# Power.net
KiCad netlist of a schematic drawn in Altium Designer
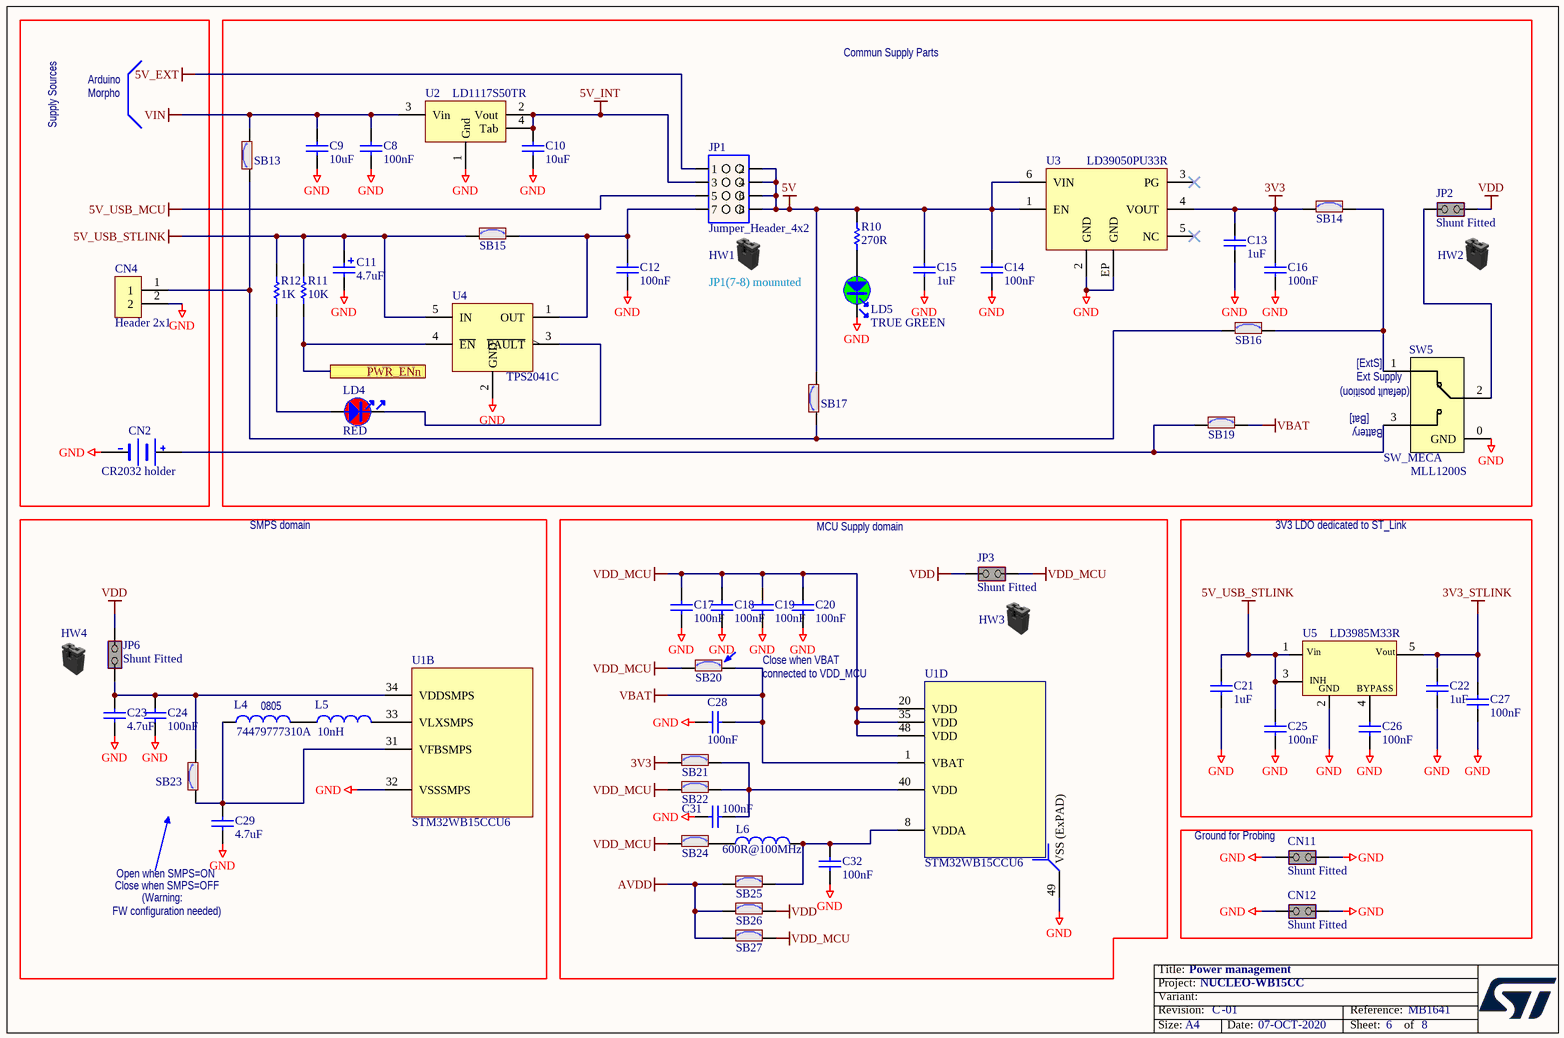
[diagram p0: Power.SchDoc]

(export (version "E")
  (design (tool "Eeschema 10.0.6"))
  (components
    (comp (ref "C8")
      (value "100nF")
      (footprint "C0603")
      (description "Capacitor, MLCC, 100nF, 50V, X7R, +/-10%, 0603, T=0.8mm")
      (fields
        (field (name "INTERNAL_PART_NUMBER") "MCD-01099")
        (field (name "MANUFACTURER_PART_NUMBER") "CC0603KRX7R9BB104")
      )
      (libsource (lib "MCD_PARTS_database") (part "Capacitor"))
    )
    (comp (ref "C9")
      (value "10uF")
      (footprint "C0805")
      (description "Capacitor, MLCC, 10uF, 25V, X5R, +/-10%, 0805, T=0,85mm")
      (fields
        (field (name "INTERNAL_PART_NUMBER") "MCD-00014")
        (field (name "MANUFACTURER_PART_NUMBER") "CC0805KRX5R8BB106")
      )
      (libsource (lib "MCD_PARTS_database") (part "Capacitor"))
    )
    (comp (ref "C10")
      (value "10uF")
      (footprint "C0805")
      (description "Capacitor, MLCC, 10uF, 25V, X5R, +/-10%, 0805, T=0,85mm")
      (fields
        (field (name "INTERNAL_PART_NUMBER") "MCD-00014")
        (field (name "MANUFACTURER_PART_NUMBER") "CC0805KRX5R8BB106")
      )
      (libsource (lib "MCD_PARTS_database") (part "Capacitor"))
    )
    (comp (ref "C11")
      (value "4.7uF")
      (footprint "CPOL_TAJ-A_1206_H180")
      (description "Capacitor, Tantalum, 4.7uF, 16V, 4ohms, +/-10%, pkg Type_A (3216 metric), T=1.6mm")
      (fields
        (field (name "INTERNAL_PART_NUMBER") "MCD-00007")
        (field (name "MANUFACTURER_PART_NUMBER") "TAJA475K016R")
      )
      (libsource (lib "MCD_PARTS_database") (part "Cap_POL_TANA"))
    )
    (comp (ref "C12")
      (value "100nF")
      (footprint "C0402")
      (description "Capacitor, MLCC, 100nF, 16V, X7R, +/-10%, 0402, T=0.5mm")
      (fields
        (field (name "INTERNAL_PART_NUMBER") "MCD-00006")
        (field (name "MANUFACTURER_PART_NUMBER") "CC0402KRX7R7BB104")
      )
      (libsource (lib "MCD_PARTS_database") (part "Capacitor"))
    )
    (comp (ref "C13")
      (value "1uF")
      (footprint "C0603")
      (description "Capacitor, MLCC, 1uF, 16V, X5R, +/-10%, 0603, T=0,8mm")
      (fields
        (field (name "INTERNAL_PART_NUMBER") "MCD-00010")
        (field (name "MANUFACTURER_PART_NUMBER") "CC0603KRX5R7BB105")
      )
      (libsource (lib "MCD_PARTS_database") (part "Capacitor"))
    )
    (comp (ref "C14")
      (value "100nF")
      (footprint "C0402")
      (description "Capacitor, MLCC, 100nF, 16V, X7R, +/-10%, 0402, T=0.5mm")
      (fields
        (field (name "INTERNAL_PART_NUMBER") "MCD-00006")
        (field (name "MANUFACTURER_PART_NUMBER") "CC0402KRX7R7BB104")
      )
      (libsource (lib "MCD_PARTS_database") (part "Capacitor"))
    )
    (comp (ref "C15")
      (value "1uF")
      (footprint "C0603")
      (description "Capacitor, MLCC, 1uF, 16V, X5R, +/-10%, 0603, T=0,8mm")
      (fields
        (field (name "INTERNAL_PART_NUMBER") "MCD-00010")
        (field (name "MANUFACTURER_PART_NUMBER") "CC0603KRX5R7BB105")
      )
      (libsource (lib "MCD_PARTS_database") (part "Capacitor"))
    )
    (comp (ref "C16")
      (value "100nF")
      (footprint "C0402")
      (description "Capacitor, MLCC, 100nF, 16V, X7R, +/-10%, 0402, T=0.5mm")
      (fields
        (field (name "INTERNAL_PART_NUMBER") "MCD-00006")
        (field (name "MANUFACTURER_PART_NUMBER") "CC0402KRX7R7BB104")
      )
      (libsource (lib "MCD_PARTS_database") (part "Capacitor"))
    )
    (comp (ref "C17")
      (value "100nF")
      (footprint "C0402")
      (description "Capacitor, MLCC, 100nF, 16V, X7R, +/-10%, 0402, T=0.5mm")
      (fields
        (field (name "INTERNAL_PART_NUMBER") "MCD-00006")
        (field (name "MANUFACTURER_PART_NUMBER") "CC0402KRX7R7BB104")
      )
      (libsource (lib "MCD_PARTS_database") (part "Capacitor"))
    )
    (comp (ref "C18")
      (value "100nF")
      (footprint "C0402")
      (description "Capacitor, MLCC, 100nF, 16V, X7R, +/-10%, 0402, T=0.5mm")
      (fields
        (field (name "INTERNAL_PART_NUMBER") "MCD-00006")
        (field (name "MANUFACTURER_PART_NUMBER") "CC0402KRX7R7BB104")
      )
      (libsource (lib "MCD_PARTS_database") (part "Capacitor"))
    )
    (comp (ref "C19")
      (value "100nF")
      (footprint "C0402")
      (description "Capacitor, MLCC, 100nF, 16V, X7R, +/-10%, 0402, T=0.5mm")
      (fields
        (field (name "INTERNAL_PART_NUMBER") "MCD-00006")
        (field (name "MANUFACTURER_PART_NUMBER") "CC0402KRX7R7BB104")
      )
      (libsource (lib "MCD_PARTS_database") (part "Capacitor"))
    )
    (comp (ref "C20")
      (value "100nF")
      (footprint "C0402")
      (description "Capacitor, MLCC, 100nF, 16V, X7R, +/-10%, 0402, T=0.5mm")
      (fields
        (field (name "INTERNAL_PART_NUMBER") "MCD-00006")
        (field (name "MANUFACTURER_PART_NUMBER") "CC0402KRX7R7BB104")
      )
      (libsource (lib "MCD_PARTS_database") (part "Capacitor"))
    )
    (comp (ref "C21")
      (value "1uF")
      (footprint "C0603")
      (description "Capacitor, MLCC, 1uF, 16V, X5R, +/-10%, 0603, T=0,8mm")
      (fields
        (field (name "INTERNAL_PART_NUMBER") "MCD-00010")
        (field (name "MANUFACTURER_PART_NUMBER") "CC0603KRX5R7BB105")
      )
      (libsource (lib "MCD_PARTS_database") (part "Capacitor"))
    )
    (comp (ref "C22")
      (value "1uF")
      (footprint "C0603")
      (description "Capacitor, MLCC, 1uF, 16V, X5R, +/-10%, 0603, T=0,8mm")
      (fields
        (field (name "INTERNAL_PART_NUMBER") "MCD-00010")
        (field (name "MANUFACTURER_PART_NUMBER") "CC0603KRX5R7BB105")
      )
      (libsource (lib "MCD_PARTS_database") (part "Capacitor"))
    )
    (comp (ref "C23")
      (value "4.7uF")
      (footprint "C0402")
      (description "Capacitor, MLCC, 4.7uF, 6V3, X5R, +/-20%, 0402, T=0,5mm")
      (fields
        (field (name "INTERNAL_PART_NUMBER") "MCD-01356")
        (field (name "MANUFACTURER_PART_NUMBER") "GRM155R60J475ME47")
      )
      (libsource (lib "MCD_PARTS_database") (part "Capacitor"))
    )
    (comp (ref "C24")
      (value "100nF")
      (footprint "C0402")
      (description "Capacitor, MLCC, 100nF, 16V, X7R, +/-10%, 0402, T=0.5mm")
      (fields
        (field (name "INTERNAL_PART_NUMBER") "MCD-00006")
        (field (name "MANUFACTURER_PART_NUMBER") "CC0402KRX7R7BB104")
      )
      (libsource (lib "MCD_PARTS_database") (part "Capacitor"))
    )
    (comp (ref "C25")
      (value "100nF")
      (footprint "C0402")
      (description "Capacitor, MLCC, 100nF, 16V, X7R, +/-10%, 0402, T=0.5mm")
      (fields
        (field (name "INTERNAL_PART_NUMBER") "MCD-00006")
        (field (name "MANUFACTURER_PART_NUMBER") "CC0402KRX7R7BB104")
      )
      (libsource (lib "MCD_PARTS_database") (part "Capacitor"))
    )
    (comp (ref "C26")
      (value "100nF")
      (footprint "C0402")
      (description "Capacitor, MLCC, 100nF, 16V, X7R, +/-10%, 0402, T=0.5mm")
      (fields
        (field (name "INTERNAL_PART_NUMBER") "MCD-00006")
        (field (name "MANUFACTURER_PART_NUMBER") "CC0402KRX7R7BB104")
      )
      (libsource (lib "MCD_PARTS_database") (part "Capacitor"))
    )
    (comp (ref "C27")
      (value "100nF")
      (footprint "C0402")
      (description "Capacitor, MLCC, 100nF, 16V, X7R, +/-10%, 0402, T=0.5mm")
      (fields
        (field (name "INTERNAL_PART_NUMBER") "MCD-00006")
        (field (name "MANUFACTURER_PART_NUMBER") "CC0402KRX7R7BB104")
      )
      (libsource (lib "MCD_PARTS_database") (part "Capacitor"))
    )
    (comp (ref "C28")
      (value "100nF")
      (footprint "C0402")
      (description "Capacitor, MLCC, 100nF, 16V, X7R, +/-10%, 0402, T=0.5mm")
      (fields
        (field (name "INTERNAL_PART_NUMBER") "MCD-00006")
        (field (name "MANUFACTURER_PART_NUMBER") "CC0402KRX7R7BB104")
      )
      (libsource (lib "MCD_PARTS_database") (part "Capacitor"))
    )
    (comp (ref "C29")
      (value "4.7uF")
      (footprint "C0402")
      (description "Capacitor, MLCC, 4.7uF, 6V3, X5R, +/-20%, 0402, T=0,5mm")
      (fields
        (field (name "INTERNAL_PART_NUMBER") "MCD-01356")
        (field (name "MANUFACTURER_PART_NUMBER") "GRM155R60J475ME47")
      )
      (libsource (lib "MCD_PARTS_database") (part "Capacitor"))
    )
    (comp (ref "C31")
      (value "100nF")
      (footprint "C0402")
      (description "Capacitor, MLCC, 100nF, 16V, X7R, +/-10%, 0402, T=0.5mm")
      (fields
        (field (name "INTERNAL_PART_NUMBER") "MCD-00006")
        (field (name "MANUFACTURER_PART_NUMBER") "CC0402KRX7R7BB104")
      )
      (libsource (lib "MCD_PARTS_database") (part "Capacitor"))
    )
    (comp (ref "C32")
      (value "100nF")
      (footprint "C0402")
      (description "Capacitor, MLCC, 100nF, 16V, X7R, +/-10%, 0402, T=0.5mm")
      (fields
        (field (name "INTERNAL_PART_NUMBER") "MCD-00006")
        (field (name "MANUFACTURER_PART_NUMBER") "CC0402KRX7R7BB104")
      )
      (libsource (lib "MCD_PARTS_database") (part "Capacitor"))
    )
    (comp (ref "CN2")
      (value "CR2032 holder")
      (footprint "BAT_RENATA-SMTU2032-LF_KEYSTONE-1769533_CR2032_SMD_2P_DI")
      (description "Battery Coin Cell holder, CR2032_20mm, Height 5.4mm")
      (fields
        (field (name "INTERNAL_PART_NUMBER") "MCD-02071")
        (field (name "MANUFACTURER_PART_NUMBER") "SMTU2032-LF")
      )
      (libsource (lib "MCD_PARTS_database") (part "BATTERY HOLDER"))
    )
    (comp (ref "CN4")
      (value "Header 2x1")
      (footprint "CON_SAMTEC_TSW-102-07-G-S")
      (description "Header, 2x1, 2,54mm, VR, TH, Height 5.84mm/2.54mm")
      (fields
        (field (name "INTERNAL_PART_NUMBER") "MCD-00032")
        (field (name "MANUFACTURER_PART_NUMBER") "TSW-102-07-G-S")
      )
      (libsource (lib "MCD_PARTS_database") (part "Header 2x1"))
    )
    (comp (ref "CN11")
      (value "Shunt Fitted")
      (footprint "CON_SAMTEC_TSW-102-07-G-S")
      (description "Header, 2x1, 2,54mm, VR, TH, Height 5.84mm/2.54mm - Shunt Fitted by default")
      (fields
        (field (name "INTERNAL_PART_NUMBER") "MCD-00683")
        (field (name "MANUFACTURER_PART_NUMBER") "TSW-102-07-G-S")
      )
      (libsource (lib "") (part "Jumper_Header 2x1 Fitted_1"))
    )
    (comp (ref "CN12")
      (value "Shunt Fitted")
      (footprint "CON_SAMTEC_TSW-102-07-G-S")
      (description "Header, 2x1, 2,54mm, VR, TH, Height 5.84mm/2.54mm - Shunt Fitted by default")
      (fields
        (field (name "INTERNAL_PART_NUMBER") "MCD-00683")
        (field (name "MANUFACTURER_PART_NUMBER") "TSW-102-07-G-S")
      )
      (libsource (lib "") (part "Jumper_Header 2x1 Fitted_1"))
    )
    (comp (ref "HW1")
      (value "Shunt Black 2.54mm")
      (description "SHUNT 2.54mm BLACK")
      (fields
        (field (name "INTERNAL_PART_NUMBER") "MCD-00043")
        (field (name "MANUFACTURER_PART_NUMBER") "SNT-100-BK-G")
      )
      (libsource (lib "MCD_PARTS_database") (part "Shunt Black 2.54mm"))
    )
    (comp (ref "HW2")
      (value "Shunt Black 2.54mm")
      (description "SHUNT 2.54mm BLACK")
      (fields
        (field (name "INTERNAL_PART_NUMBER") "MCD-00043")
        (field (name "MANUFACTURER_PART_NUMBER") "SNT-100-BK-G")
      )
      (libsource (lib "MCD_PARTS_database") (part "Shunt Black 2.54mm"))
    )
    (comp (ref "HW3")
      (value "Shunt Black 2.54mm")
      (description "SHUNT 2.54mm BLACK")
      (fields
        (field (name "INTERNAL_PART_NUMBER") "MCD-00043")
        (field (name "MANUFACTURER_PART_NUMBER") "SNT-100-BK-G")
      )
      (libsource (lib "MCD_PARTS_database") (part "Shunt Black 2.54mm"))
    )
    (comp (ref "HW4")
      (value "Shunt Black 2.54mm")
      (description "SHUNT 2.54mm BLACK")
      (fields
        (field (name "INTERNAL_PART_NUMBER") "MCD-00043")
        (field (name "MANUFACTURER_PART_NUMBER") "SNT-100-BK-G")
      )
      (libsource (lib "MCD_PARTS_database") (part "Shunt Black 2.54mm"))
    )
    (comp (ref "JP1")
      (value "Jumper_Header_4x2")
      (footprint "CON_SAMTEC_TSW-104-07-X-D")
      (description "Header, 4x2, 2,54mm, VR, TH, Height 5.84mm/2.54mm")
      (fields
        (field (name "INTERNAL_PART_NUMBER") "MCD-00633")
        (field (name "MANUFACTURER_PART_NUMBER") "TSW-104-07-G-D")
      )
      (libsource (lib "MCD_PARTS_database") (part "Jumper_Header 4x2"))
    )
    (comp (ref "JP2")
      (value "Shunt Fitted")
      (footprint "CON_SAMTEC_TSW-102-07-G-S")
      (description "Header, 2x1, 2,54mm, VR, TH, Height 5.84mm/2.54mm - Shunt Fitted by default")
      (fields
        (field (name "INTERNAL_PART_NUMBER") "MCD-00683")
        (field (name "MANUFACTURER_PART_NUMBER") "TSW-102-07-G-S")
      )
      (libsource (lib "") (part "Jumper_Header 2x1 Fitted_2"))
    )
    (comp (ref "JP3")
      (value "Shunt Fitted")
      (footprint "CON_SAMTEC_TSW-102-07-G-S")
      (description "Header, 2x1, 2,54mm, VR, TH, Height 5.84mm/2.54mm - Shunt Fitted by default")
      (fields
        (field (name "INTERNAL_PART_NUMBER") "MCD-00683")
        (field (name "MANUFACTURER_PART_NUMBER") "TSW-102-07-G-S")
      )
      (libsource (lib "") (part "Jumper_Header 2x1 Fitted_2"))
    )
    (comp (ref "JP6")
      (value "Shunt Fitted")
      (footprint "CON_SAMTEC_TSW-102-07-G-S")
      (description "Header, 2x1, 2,54mm, VR, TH, Height 5.84mm/2.54mm - Shunt Fitted by default")
      (fields
        (field (name "INTERNAL_PART_NUMBER") "MCD-00683")
        (field (name "MANUFACTURER_PART_NUMBER") "TSW-102-07-G-S")
      )
      (libsource (lib "MCD_PARTS_database") (part "Jumper_Header 2x1 Fitted"))
    )
    (comp (ref "L4")
      (value "74479777310A")
      (footprint "IND_0805_WURTH_74479777310A")
      (description "PMI Series 10 μH ±20% Multilayer SMD Inductor, 0805 25MHz 650mA dc 500mΩ Rdc")
      (fields
        (field (name "INTERNAL_PART_NUMBER") "MCD-01676")
        (field (name "MANUFACTURER") "WURTH ELEKTRONIK")
      )
      (libsource (lib "MCD_PARTS_database") (part "Inductor"))
    )
    (comp (ref "L5")
      (value "10nH")
      (footprint "IND_0402_MURATA_LQW15AN_H0P5")
      (description "Inductor, 10nH +-2%, 100mA max,1.3 ohm DC max, Q min = 13,0402")
      (fields
        (field (name "INTERNAL_PART_NUMBER") "MCD-02063")
        (field (name "MANUFACTURER_PART_NUMBER") "LQP15MN10NG02")
      )
      (libsource (lib "MCD_PARTS_database") (part "Inductor"))
    )
    (comp (ref "L6")
      (value "600R@100MHz")
      (footprint "L0603")
      (description "SMD Chip ferrite bead, 600R@100MHz +/-25%, 350mA, 500mohm DC, 0603, T=0.8mm")
      (fields
        (field (name "INTERNAL_PART_NUMBER") "MCD-00047")
        (field (name "MANUFACTURER_PART_NUMBER") "FCM1608KF-601T03")
      )
      (libsource (lib "MCD_PARTS_database") (part "BEAD"))
    )
    (comp (ref "LD4")
      (value "RED")
      (footprint "LED_0603_VISHAY_VLMS1300-GS08_RED_1A2K_H0P8")
      (description "LED Red, 0603 SMD, 2V Forward Voltage")
      (fields
        (field (name "INTERNAL_PART_NUMBER") "MCD-00587")
        (field (name "MANUFACTURER_PART_NUMBER") "VLMS1300-GS08")
      )
      (libsource (lib "MCD_PARTS_database") (part "LED_red"))
    )
    (comp (ref "LD5")
      (value "TRUE GREEN")
      (footprint "LED_0603_VISHAY_VLMTG1300-GS08_GREEN_1A2K_H0P8")
      (description "LED Green, 0603 SMD, Fw Voltage = 2.8V - 3.6V")
      (fields
        (field (name "INTERNAL_PART_NUMBER") "MCD-00589")
        (field (name "MANUFACTURER_PART_NUMBER") "VLMTG1300-GS08")
      )
      (libsource (lib "MCD_PARTS_database") (part "LED_green"))
    )
    (comp (ref "R10")
      (value "270R")
      (footprint "R0402")
      (description "Resistor,270R,0402,1%,1/16W")
      (fields
        (field (name "INTERNAL_PART_NUMBER") "MCD-00441")
        (field (name "MANUFACTURER_PART_NUMBER") "RC0402FR-07270RL")
      )
      (libsource (lib "MCD_PARTS_database") (part "Resistor"))
    )
    (comp (ref "R11")
      (value "10K")
      (footprint "R0402")
      (description "Resistor,10K,0402,1%,1/16W")
      (fields
        (field (name "INTERNAL_PART_NUMBER") "MCD-00053")
        (field (name "MANUFACTURER_PART_NUMBER") "RC0402FR-0710KL")
      )
      (libsource (lib "MCD_PARTS_database") (part "Resistor"))
    )
    (comp (ref "R12")
      (value "1K")
      (footprint "R0402")
      (description "Resistor,1K,0402,1%,1/16W")
      (fields
        (field (name "INTERNAL_PART_NUMBER") "MCD-00061")
        (field (name "MANUFACTURER_PART_NUMBER") "RC0402FR-071KL")
      )
      (libsource (lib "MCD_PARTS_database") (part "Resistor"))
    )
    (comp (ref "SB13")
      (value "SB_ON")
      (footprint "SOLDER-BRIDGE_R0402-0R")
      (description "Solder Bridge 0402 ON")
      (fields
        (field (name "INTERNAL_PART_NUMBER") "MCD-01618")
        (field (name "MANUFACTURER_PART_NUMBER") "RC0402JR-070RL")
      )
      (libsource (lib "MCD_PARTS_database") (part "SB_ON"))
    )
    (comp (ref "SB14")
      (value "SB_ON")
      (footprint "SOLDER-BRIDGE_R0402-0R")
      (description "Solder Bridge 0402 ON")
      (fields
        (field (name "INTERNAL_PART_NUMBER") "MCD-01618")
        (field (name "MANUFACTURER_PART_NUMBER") "RC0402JR-070RL")
      )
      (libsource (lib "") (part "SB_ON_1"))
    )
    (comp (ref "SB15")
      (value "SB_ON")
      (footprint "SOLDER-BRIDGE_R0402-0R")
      (description "Solder Bridge 0402 ON")
      (fields
        (field (name "INTERNAL_PART_NUMBER") "MCD-01618")
        (field (name "MANUFACTURER_PART_NUMBER") "RC0402JR-070RL")
      )
      (libsource (lib "") (part "SB_ON_1"))
    )
    (comp (ref "SB16")
      (value "SB_ON")
      (footprint "SOLDER-BRIDGE_R0402-0R")
      (description "Solder Bridge 0402 ON")
      (fields
        (field (name "INTERNAL_PART_NUMBER") "MCD-01618")
        (field (name "MANUFACTURER_PART_NUMBER") "RC0402JR-070RL")
      )
      (libsource (lib "") (part "SB_ON_1"))
    )
    (comp (ref "SB17")
      (value "SB_ON")
      (footprint "SOLDER-BRIDGE_R0402-0R")
      (description "Solder Bridge 0402 ON")
      (fields
        (field (name "INTERNAL_PART_NUMBER") "MCD-01618")
        (field (name "MANUFACTURER_PART_NUMBER") "RC0402JR-070RL")
      )
      (libsource (lib "MCD_PARTS_database") (part "SB_ON"))
    )
    (comp (ref "SB19")
      (value "SB_ON")
      (footprint "SOLDER-BRIDGE_R0402-0R")
      (description "Solder Bridge 0402 ON")
      (fields
        (field (name "INTERNAL_PART_NUMBER") "MCD-01618")
        (field (name "MANUFACTURER_PART_NUMBER") "RC0402JR-070RL")
      )
      (libsource (lib "") (part "SB_ON_1"))
    )
    (comp (ref "SB20")
      (value "SB_ON")
      (footprint "SOLDER-BRIDGE_R0402-0R")
      (description "Solder Bridge 0402 ON")
      (fields
        (field (name "INTERNAL_PART_NUMBER") "MCD-01618")
        (field (name "MANUFACTURER_PART_NUMBER") "RC0402JR-070RL")
      )
      (libsource (lib "") (part "SB_ON_1"))
    )
    (comp (ref "SB21")
      (value "SB_ON")
      (footprint "SOLDER-BRIDGE_R0402-0R")
      (description "Solder Bridge 0402 ON")
      (fields
        (field (name "INTERNAL_PART_NUMBER") "MCD-01618")
        (field (name "MANUFACTURER_PART_NUMBER") "RC0402JR-070RL")
      )
      (libsource (lib "") (part "SB_ON_1"))
    )
    (comp (ref "SB22")
      (value "SB_ON")
      (footprint "SOLDER-BRIDGE_R0402-0R")
      (description "Solder Bridge 0402 ON")
      (fields
        (field (name "INTERNAL_PART_NUMBER") "MCD-01618")
        (field (name "MANUFACTURER_PART_NUMBER") "RC0402JR-070RL")
      )
      (libsource (lib "") (part "SB_ON_1"))
    )
    (comp (ref "SB23")
      (value "SB_ON")
      (footprint "SOLDER-BRIDGE_R0402-0R")
      (description "Solder Bridge 0402 ON")
      (fields
        (field (name "INTERNAL_PART_NUMBER") "MCD-01618")
        (field (name "MANUFACTURER_PART_NUMBER") "RC0402JR-070RL")
      )
      (libsource (lib "MCD_PARTS_database") (part "SB_ON"))
    )
    (comp (ref "SB24")
      (value "SB_ON")
      (footprint "SOLDER-BRIDGE_R0402-0R")
      (description "Solder Bridge 0402 ON")
      (fields
        (field (name "INTERNAL_PART_NUMBER") "MCD-01618")
        (field (name "MANUFACTURER_PART_NUMBER") "RC0402JR-070RL")
      )
      (libsource (lib "") (part "SB_ON_1"))
    )
    (comp (ref "SB25")
      (value "SB_ON")
      (footprint "SOLDER-BRIDGE_R0402-0R")
      (description "Solder Bridge 0402 ON")
      (fields
        (field (name "INTERNAL_PART_NUMBER") "MCD-01618")
        (field (name "MANUFACTURER_PART_NUMBER") "RC0402JR-070RL")
      )
      (libsource (lib "") (part "SB_ON_1"))
    )
    (comp (ref "SB26")
      (value "SB_ON")
      (footprint "SOLDER-BRIDGE_R0402-0R")
      (description "Solder Bridge 0402 ON")
      (fields
        (field (name "INTERNAL_PART_NUMBER") "MCD-01618")
        (field (name "MANUFACTURER_PART_NUMBER") "RC0402JR-070RL")
      )
      (libsource (lib "") (part "SB_ON_1"))
    )
    (comp (ref "SB27")
      (value "SB_ON")
      (footprint "SOLDER-BRIDGE_R0402-0R")
      (description "Solder Bridge 0402 ON")
      (fields
        (field (name "INTERNAL_PART_NUMBER") "MCD-01618")
        (field (name "MANUFACTURER_PART_NUMBER") "RC0402JR-070RL")
      )
      (libsource (lib "") (part "SB_ON_1"))
    )
    (comp (ref "SW5")
      (value "SW_MECA")
      (footprint "SWI_SPDT-RA_TE-CONNECTIVITY_MLL1200S_1P2T")
      (description "SPDT RA SMT SLIDE SWITCH")
      (fields
        (field (name "INTERNAL_PART_NUMBER") "MCD-02081")
        (field (name "ALTIUM_VALUE") "MLL1200S")
        (field (name "MANUFACTURER_PART_NUMBER") "MLL1200S")
      )
      (libsource (lib "MCD_PARTS_database") (part "SW_MECA"))
    )
    (comp (ref "U1")
      (value "STM32WB15CCU6")
      (footprint "ICC_UFQFPN48-EPAD_7X7_H0P55_P050")
      (fields
        (field (name "INTERNAL_PART_NUMBER") "MCD-02058")
        (field (name "MANUFACTURER") "STMICROELECTRONICS")
        (field (name "Comment") "STM32WB15_QFN48")
      )
      (libsource (lib "MCD_PARTS_database") (part "STM32WB15_QFN48"))
    )
    (comp (ref "U2")
      (value "LD1117S50TR")
      (footprint "REG_SOT223-TAB")
      (description "IC REG LDO 5V 0.8A SOT223")
      (fields
        (field (name "INTERNAL_PART_NUMBER") "MCD-00088")
        (field (name "MANUFACTURER") "STMICROELECTRONICS")
      )
      (libsource (lib "MCD_PARTS_database") (part "LD1117S50TR"))
    )
    (comp (ref "U3")
      (value "LD39050PU33R")
      (footprint "ICC_DFN6-EPAD_3X3_P095")
      (description "Low quiescent current and low noise voltage regulators")
      (fields
        (field (name "INTERNAL_PART_NUMBER") "MCD-00215")
        (field (name "MANUFACTURER") "STMICROELECTRONICS")
      )
      (libsource (lib "MCD_PARTS_database") (part "LD39050PU33R"))
    )
    (comp (ref "U4")
      (value "TPS2041C")
      (footprint "MOS_SOT23-5L")
      (description "5V Power Switch, 0.85A, RDSon 130mOhm max, with active low enable pin")
      (fields
        (field (name "INTERNAL_PART_NUMBER") "MCD-01785")
        (field (name "MANUFACTURER_PART_NUMBER") "TPS2041CDBVT")
      )
      (libsource (lib "MCD_PARTS_database") (part "TPS2041C"))
    )
    (comp (ref "U5")
      (value "LD3985M33R")
      (footprint "REG_SOT23-5L")
      (description "Ultra low drop-low noise BiCMOS voltage, regulators low ESR capacitors compatible")
      (fields
        (field (name "INTERNAL_PART_NUMBER") "MCD-00086")
        (field (name "MANUFACTURER") "STMICROELECTRONICS")
      )
      (libsource (lib "MCD_PARTS_database") (part "LD3985M33R"))
    )
  )
  (nets
    (net (code "1") (name "/PWR_ENn") (class "Default")
      (node (ref "R11") (pin "1") (pinfunction "1_1") (pintype "passive"))
      (node (ref "U4") (pin "4") (pinfunction "~{EN}_4") (pintype "passive"))
    )
    (net (code "2") (name "3V3") (class "Default")
      (node (ref "C13") (pin "2") (pinfunction "2_2") (pintype "passive"))
      (node (ref "C16") (pin "2") (pinfunction "2_2") (pintype "passive"))
      (node (ref "SB14") (pin "1") (pinfunction "1_1") (pintype "passive"))
      (node (ref "SB21") (pin "1") (pinfunction "1_1") (pintype "passive"))
      (node (ref "U3") (pin "4") (pinfunction "VOUT_4") (pintype "passive"))
    )
    (net (code "3") (name "3V3_STLINK") (class "Default")
      (node (ref "C22") (pin "2") (pinfunction "2_2") (pintype "passive"))
      (node (ref "C27") (pin "2") (pinfunction "2_2") (pintype "passive"))
      (node (ref "U5") (pin "5") (pinfunction "Vout_5") (pintype "passive"))
    )
    (net (code "4") (name "5V") (class "Default")
      (node (ref "C14") (pin "2") (pinfunction "2_2") (pintype "passive"))
      (node (ref "C15") (pin "2") (pinfunction "2_2") (pintype "passive"))
      (node (ref "JP1") (pin "2") (pinfunction "2_2") (pintype "passive"))
      (node (ref "JP1") (pin "4") (pinfunction "4_4") (pintype "passive"))
      (node (ref "JP1") (pin "6") (pinfunction "6_6") (pintype "passive"))
      (node (ref "JP1") (pin "8") (pinfunction "8_8") (pintype "passive"))
      (node (ref "R10") (pin "2") (pinfunction "2_2") (pintype "passive"))
      (node (ref "SB17") (pin "2") (pinfunction "2_2") (pintype "passive"))
      (node (ref "U3") (pin "1") (pinfunction "EN_1") (pintype "passive"))
      (node (ref "U3") (pin "6") (pinfunction "VIN_6") (pintype "passive"))
    )
    (net (code "5") (name "5V_EXT") (class "Default")
      (node (ref "JP1") (pin "1") (pinfunction "1_1") (pintype "passive"))
    )
    (net (code "6") (name "5V_INT") (class "Default")
      (node (ref "C10") (pin "1") (pinfunction "1_1") (pintype "passive"))
      (node (ref "JP1") (pin "3") (pinfunction "3_3") (pintype "passive"))
      (node (ref "U2") (pin "2") (pinfunction "Vout_2") (pintype "passive"))
      (node (ref "U2") (pin "4") (pinfunction "Tab_4") (pintype "passive"))
    )
    (net (code "7") (name "5V_USB_MCU") (class "Default")
      (node (ref "JP1") (pin "5") (pinfunction "5_5") (pintype "passive"))
    )
    (net (code "8") (name "5V_USB_STLINK") (class "Default")
      (node (ref "C11") (pin "1") (pinfunction "1_1") (pintype "passive"))
      (node (ref "C21") (pin "2") (pinfunction "2_2") (pintype "passive"))
      (node (ref "C25") (pin "2") (pinfunction "2_2") (pintype "passive"))
      (node (ref "R11") (pin "2") (pinfunction "2_2") (pintype "passive"))
      (node (ref "R12") (pin "2") (pinfunction "2_2") (pintype "passive"))
      (node (ref "SB15") (pin "1") (pinfunction "1_1") (pintype "passive"))
      (node (ref "U4") (pin "5") (pinfunction "IN_5") (pintype "passive"))
      (node (ref "U5") (pin "1") (pinfunction "Vin_1") (pintype "passive"))
      (node (ref "U5") (pin "3") (pinfunction "CE_3") (pintype "passive"))
    )
    (net (code "9") (name "AVDD") (class "Default")
      (node (ref "SB25") (pin "1") (pinfunction "1_1") (pintype "passive"))
      (node (ref "SB26") (pin "1") (pinfunction "1_1") (pintype "passive"))
      (node (ref "SB27") (pin "1") (pinfunction "1_1") (pintype "passive"))
    )
    (net (code "10") (name "GND") (class "Default")
      (node (ref "C10") (pin "2") (pinfunction "2_2") (pintype "passive"))
      (node (ref "C11") (pin "2") (pinfunction "2_2") (pintype "passive"))
      (node (ref "C12") (pin "1") (pinfunction "1_1") (pintype "passive"))
      (node (ref "C13") (pin "1") (pinfunction "1_1") (pintype "passive"))
      (node (ref "C14") (pin "1") (pinfunction "1_1") (pintype "passive"))
      (node (ref "C15") (pin "1") (pinfunction "1_1") (pintype "passive"))
      (node (ref "C16") (pin "1") (pinfunction "1_1") (pintype "passive"))
      (node (ref "C17") (pin "1") (pinfunction "1_1") (pintype "passive"))
      (node (ref "C18") (pin "1") (pinfunction "1_1") (pintype "passive"))
      (node (ref "C19") (pin "1") (pinfunction "1_1") (pintype "passive"))
      (node (ref "C20") (pin "1") (pinfunction "1_1") (pintype "passive"))
      (node (ref "C21") (pin "1") (pinfunction "1_1") (pintype "passive"))
      (node (ref "C22") (pin "1") (pinfunction "1_1") (pintype "passive"))
      (node (ref "C23") (pin "1") (pinfunction "1_1") (pintype "passive"))
      (node (ref "C24") (pin "1") (pinfunction "1_1") (pintype "passive"))
      (node (ref "C25") (pin "1") (pinfunction "1_1") (pintype "passive"))
      (node (ref "C26") (pin "1") (pinfunction "1_1") (pintype "passive"))
      (node (ref "C27") (pin "1") (pinfunction "1_1") (pintype "passive"))
      (node (ref "C28") (pin "2") (pinfunction "2_2") (pintype "passive"))
      (node (ref "C29") (pin "1") (pinfunction "1_1") (pintype "passive"))
      (node (ref "C31") (pin "1") (pinfunction "1_1") (pintype "passive"))
      (node (ref "C32") (pin "1") (pinfunction "1_1") (pintype "passive"))
      (node (ref "C8") (pin "1") (pinfunction "1_1") (pintype "passive"))
      (node (ref "C9") (pin "2") (pinfunction "2_2") (pintype "passive"))
      (node (ref "CN11") (pin "1") (pinfunction "COMMON_1") (pintype "passive"))
      (node (ref "CN11") (pin "2") (pinfunction "NO_2") (pintype "passive"))
      (node (ref "CN12") (pin "1") (pinfunction "COMMON_1") (pintype "passive"))
      (node (ref "CN12") (pin "2") (pinfunction "NO_2") (pintype "passive"))
      (node (ref "CN2") (pin "2") (pinfunction "-_2") (pintype "passive"))
      (node (ref "CN4") (pin "2") (pinfunction "2_2") (pintype "passive"))
      (node (ref "LD5") (pin "2") (pintype "passive"))
      (node (ref "SW5") (pin "0") (pinfunction "GND_0") (pintype "passive"))
      (node (ref "U1") (pin "32") (pinfunction "VSSSMPS_32") (pintype "passive"))
      (node (ref "U1") (pin "49") (pinfunction "VSS_(ExPAD)_49") (pintype "passive"))
      (node (ref "U2") (pin "1") (pinfunction "Gnd_1") (pintype "passive"))
      (node (ref "U3") (pin "2") (pinfunction "GND_2") (pintype "passive"))
      (node (ref "U3") (pin "EP") (pinfunction "GND_EP") (pintype "passive"))
      (node (ref "U4") (pin "2") (pinfunction "GND_2") (pintype "passive"))
      (node (ref "U5") (pin "2") (pinfunction "GND_2") (pintype "passive"))
    )
    (net (code "11") (name "Net-(C31-Pad2)") (class "Default")
      (node (ref "C31") (pin "2") (pinfunction "2_2") (pintype "passive"))
      (node (ref "SB21") (pin "2") (pinfunction "2_2") (pintype "passive"))
      (node (ref "SB22") (pin "2") (pinfunction "2_2") (pintype "passive"))
      (node (ref "U1") (pin "40") (pinfunction "VDD_40") (pintype "passive"))
    )
    (net (code "12") (name "Net-(CN2-+)") (class "Default")
      (node (ref "CN2") (pin "1") (pinfunction "+_1") (pintype "passive"))
      (node (ref "SB19") (pin "1") (pinfunction "1_1") (pintype "passive"))
      (node (ref "SW5") (pin "3") (pinfunction "3_3") (pintype "passive"))
    )
    (net (code "13") (name "Net-(CN4-Pad1)") (class "Default")
      (node (ref "CN4") (pin "1") (pinfunction "1_1") (pintype "passive"))
      (node (ref "SB13") (pin "1") (pinfunction "1_1") (pintype "passive"))
      (node (ref "SB16") (pin "1") (pinfunction "1_1") (pintype "passive"))
      (node (ref "SB17") (pin "1") (pinfunction "1_1") (pintype "passive"))
    )
    (net (code "14") (name "Net-(JP2-COMMON)") (class "Default")
      (node (ref "JP2") (pin "1") (pinfunction "COMMON_1") (pintype "passive"))
      (node (ref "SW5") (pin "2") (pinfunction "2_2") (pintype "passive"))
    )
    (net (code "15") (name "Net-(JP6-NO)") (class "Default")
      (node (ref "C23") (pin "2") (pinfunction "2_2") (pintype "passive"))
      (node (ref "C24") (pin "2") (pinfunction "2_2") (pintype "passive"))
      (node (ref "JP6") (pin "2") (pinfunction "NO_2") (pintype "passive"))
      (node (ref "SB23") (pin "2") (pinfunction "2_2") (pintype "passive"))
      (node (ref "U1") (pin "34") (pinfunction "VDDSMPS_34") (pintype "passive"))
    )
    (net (code "16") (name "Net-(L4-Pad2)") (class "Default")
      (node (ref "L4") (pin "2") (pinfunction "2_2") (pintype "passive"))
      (node (ref "L5") (pin "1") (pinfunction "1_1") (pintype "passive"))
    )
    (net (code "17") (name "Net-(L6-Pad1)") (class "Default")
      (node (ref "L6") (pin "1") (pinfunction "1_1") (pintype "passive"))
      (node (ref "SB24") (pin "2") (pinfunction "2_2") (pintype "passive"))
    )
    (net (code "18") (name "Net-(LD4-Pad1)") (class "Default")
      (node (ref "LD4") (pin "1") (pintype "passive"))
      (node (ref "R12") (pin "1") (pinfunction "1_1") (pintype "passive"))
    )
    (net (code "19") (name "Net-(LD5-Pad1)") (class "Default")
      (node (ref "LD5") (pin "1") (pintype "passive"))
      (node (ref "R10") (pin "1") (pinfunction "1_1") (pintype "passive"))
    )
    (net (code "20") (name "Net-(SB14-Pad2)") (class "Default")
      (node (ref "SB14") (pin "2") (pinfunction "2_2") (pintype "passive"))
      (node (ref "SB16") (pin "2") (pinfunction "2_2") (pintype "passive"))
      (node (ref "SW5") (pin "1") (pinfunction "1_1") (pintype "passive"))
    )
    (net (code "21") (name "Net-(U1B-VFBSMPS)") (class "Default")
      (node (ref "C29") (pin "2") (pinfunction "2_2") (pintype "passive"))
      (node (ref "L4") (pin "1") (pinfunction "1_1") (pintype "passive"))
      (node (ref "SB23") (pin "1") (pinfunction "1_1") (pintype "passive"))
      (node (ref "U1") (pin "31") (pinfunction "VFBSMPS_31") (pintype "passive"))
    )
    (net (code "22") (name "Net-(U1B-VLXSMPS)") (class "Default")
      (node (ref "L5") (pin "2") (pinfunction "2_2") (pintype "passive"))
      (node (ref "U1") (pin "33") (pinfunction "VLXSMPS_33") (pintype "passive"))
    )
    (net (code "23") (name "Net-(U1D-VDDA)") (class "Default")
      (node (ref "C32") (pin "2") (pinfunction "2_2") (pintype "passive"))
      (node (ref "L6") (pin "2") (pinfunction "2_2") (pintype "passive"))
      (node (ref "SB25") (pin "2") (pinfunction "2_2") (pintype "passive"))
      (node (ref "U1") (pin "8") (pinfunction "VDDA_8") (pintype "passive"))
    )
    (net (code "24") (name "Net-(U4-OUT)") (class "Default")
      (node (ref "C12") (pin "2") (pinfunction "2_2") (pintype "passive"))
      (node (ref "JP1") (pin "7") (pinfunction "7_7") (pintype "passive"))
      (node (ref "SB15") (pin "2") (pinfunction "2_2") (pintype "passive"))
      (node (ref "U4") (pin "1") (pinfunction "OUT_1") (pintype "passive"))
    )
    (net (code "25") (name "Net-(U4-~{FAULT})") (class "Default")
      (node (ref "LD4") (pin "2") (pintype "passive"))
      (node (ref "U4") (pin "3") (pinfunction "~{FAULT}_3") (pintype "passive"))
    )
    (net (code "26") (name "Net-(U5-BYPASS)") (class "Default")
      (node (ref "C26") (pin "2") (pinfunction "2_2") (pintype "passive"))
      (node (ref "U5") (pin "4") (pinfunction "BYPASS_4") (pintype "passive"))
    )
    (net (code "27") (name "VBAT") (class "Default")
      (node (ref "C28") (pin "1") (pinfunction "1_1") (pintype "passive"))
      (node (ref "SB19") (pin "2") (pinfunction "2_2") (pintype "passive"))
      (node (ref "SB20") (pin "2") (pinfunction "2_2") (pintype "passive"))
      (node (ref "U1") (pin "1") (pinfunction "VBAT_1") (pintype "passive"))
    )
    (net (code "28") (name "VDD") (class "Default")
      (node (ref "JP2") (pin "2") (pinfunction "NO_2") (pintype "passive"))
      (node (ref "JP3") (pin "1") (pinfunction "COMMON_1") (pintype "passive"))
      (node (ref "JP6") (pin "1") (pinfunction "COMMON_1") (pintype "passive"))
      (node (ref "SB26") (pin "2") (pinfunction "2_2") (pintype "passive"))
    )
    (net (code "29") (name "VDD_MCU") (class "Default")
      (node (ref "C17") (pin "2") (pinfunction "2_2") (pintype "passive"))
      (node (ref "C18") (pin "2") (pinfunction "2_2") (pintype "passive"))
      (node (ref "C19") (pin "2") (pinfunction "2_2") (pintype "passive"))
      (node (ref "C20") (pin "2") (pinfunction "2_2") (pintype "passive"))
      (node (ref "JP3") (pin "2") (pinfunction "NO_2") (pintype "passive"))
      (node (ref "SB20") (pin "1") (pinfunction "1_1") (pintype "passive"))
      (node (ref "SB22") (pin "1") (pinfunction "1_1") (pintype "passive"))
      (node (ref "SB24") (pin "1") (pinfunction "1_1") (pintype "passive"))
      (node (ref "SB27") (pin "2") (pinfunction "2_2") (pintype "passive"))
      (node (ref "U1") (pin "20") (pinfunction "VDD_20") (pintype "passive"))
      (node (ref "U1") (pin "35") (pinfunction "VDD_35") (pintype "passive"))
      (node (ref "U1") (pin "48") (pinfunction "VDD_48") (pintype "passive"))
    )
    (net (code "30") (name "VIN") (class "Default")
      (node (ref "C8") (pin "2") (pinfunction "2_2") (pintype "passive"))
      (node (ref "C9") (pin "1") (pinfunction "1_1") (pintype "passive"))
      (node (ref "SB13") (pin "2") (pinfunction "2_2") (pintype "passive"))
      (node (ref "U2") (pin "3") (pinfunction "Vin_3") (pintype "passive"))
    )
    (net (code "31") (name "unconnected-(U3-NC-Pad5)") (class "Default")
      (node (ref "U3") (pin "5") (pinfunction "NC_5") (pintype "passive+no_connect"))
    )
    (net (code "32") (name "unconnected-(U3-PG-Pad3)") (class "Default")
      (node (ref "U3") (pin "3") (pinfunction "PG_3") (pintype "passive+no_connect"))
    )
  )
)
